# SensorInAmp.net
KiCad netlist of a schematic drawn in Altium Designer
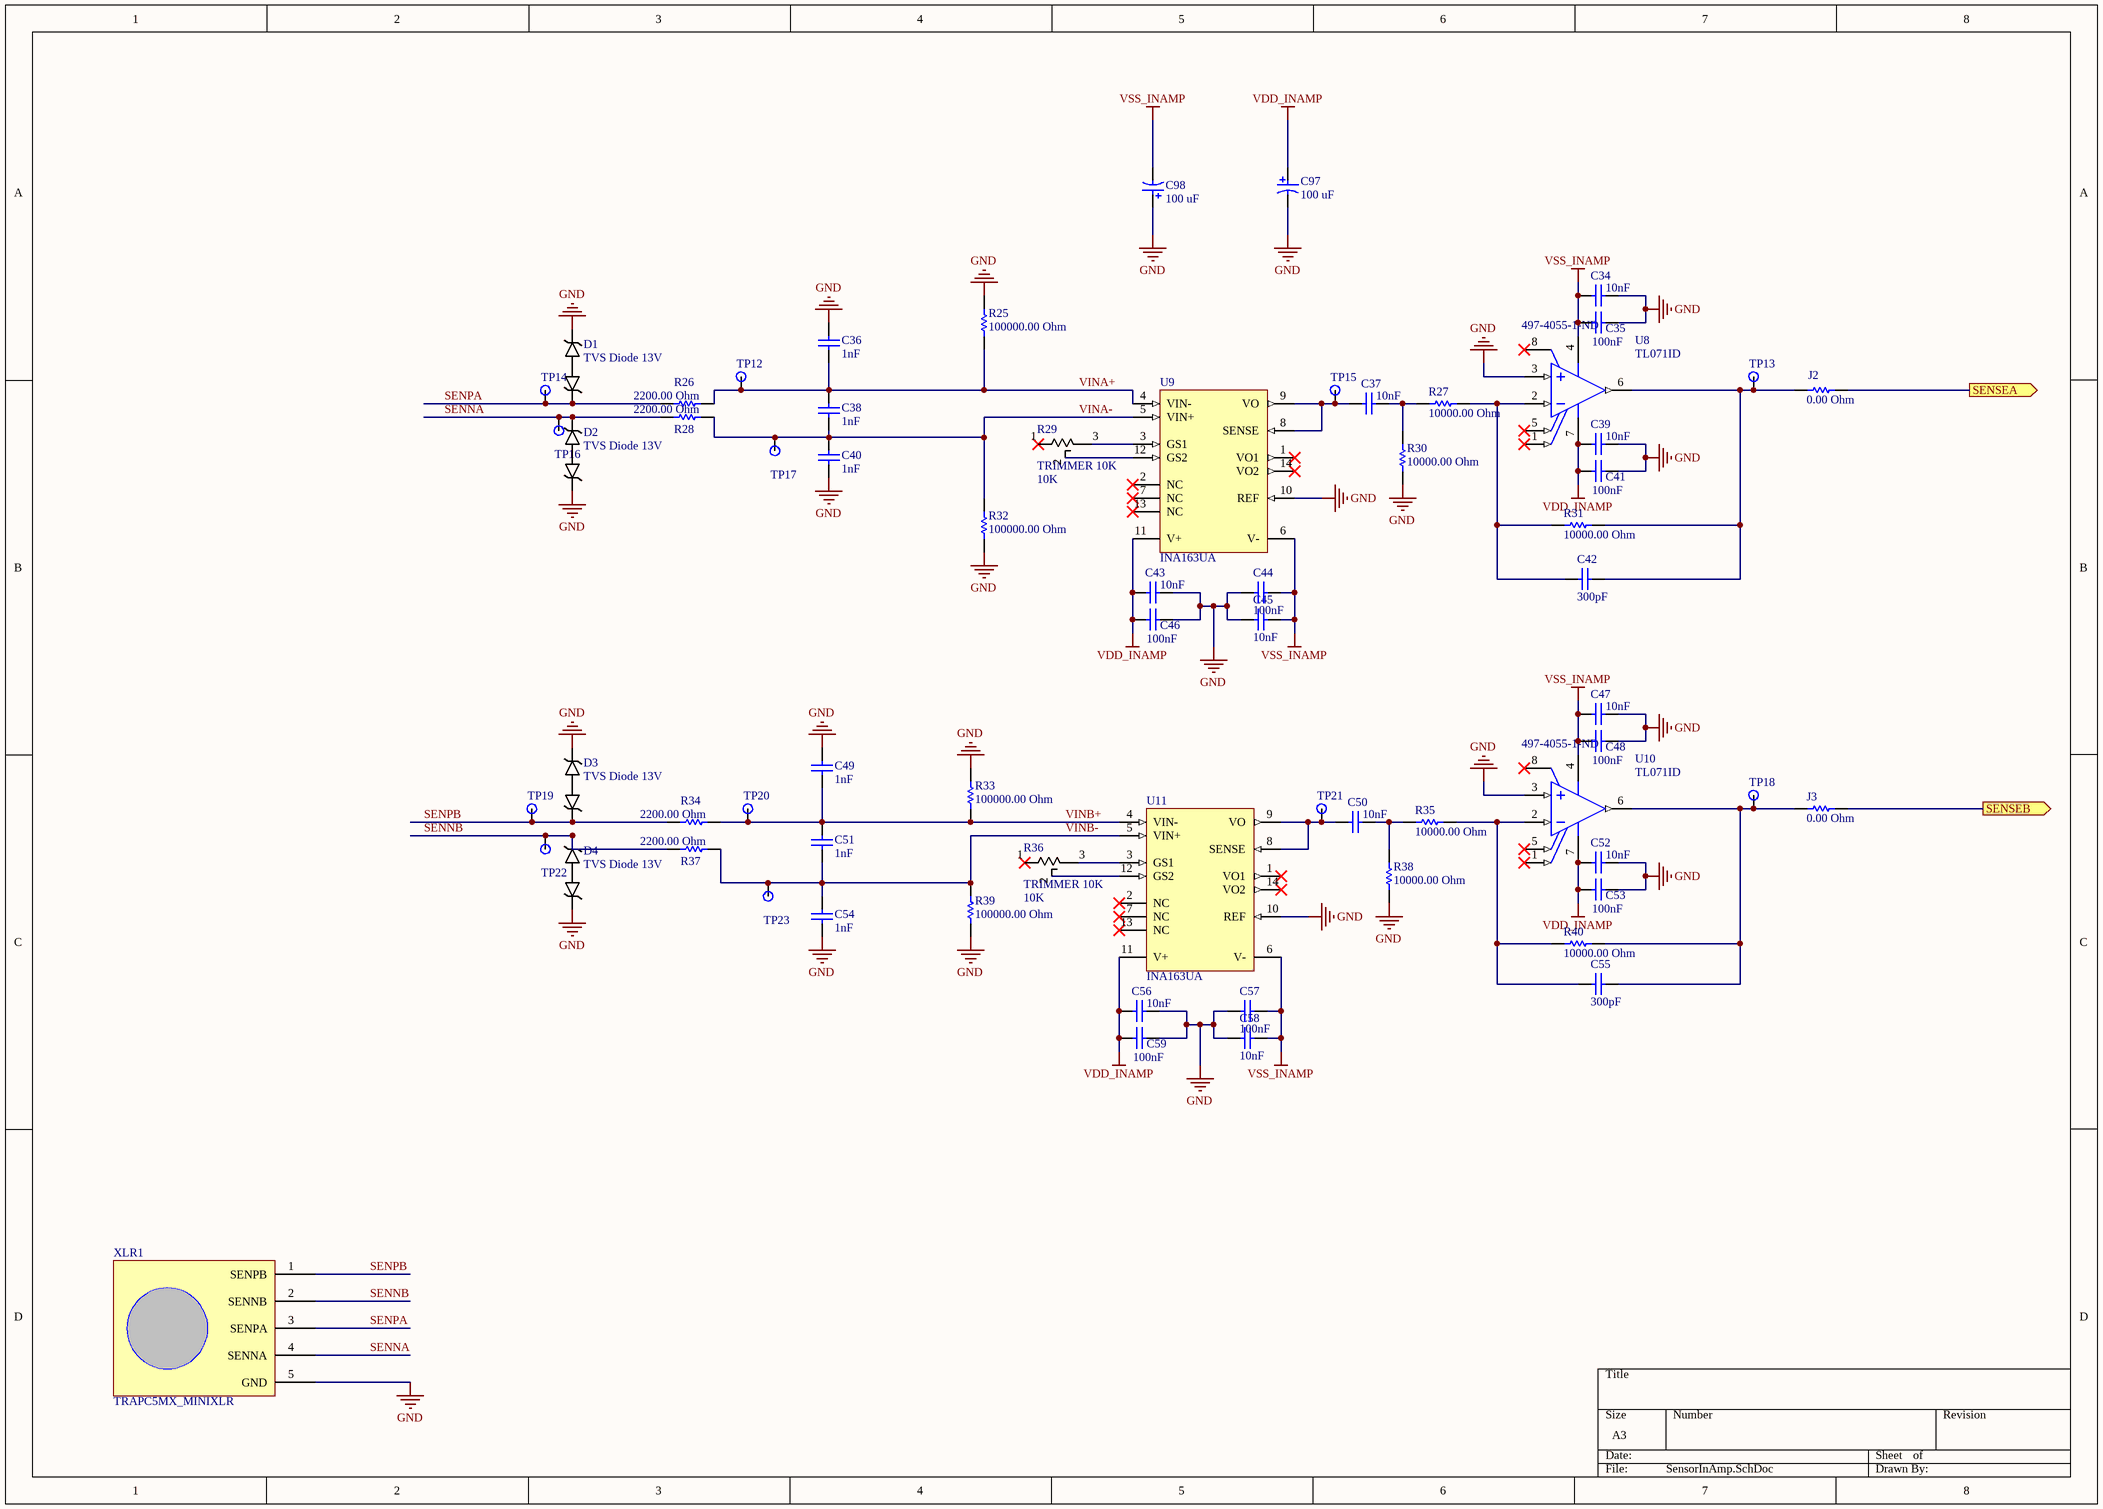
[diagram p0: SensorInAmp.SchDoc]

(export (version "E")
  (design (tool "Eeschema 10.0.6"))
  (components
    (comp (ref "C34")
      (value "10nF")
      (footprint "CAPC0603(1608)100_N")
      (description "CAP 10nF 25V ±10% 0603 (1608 Metric) Thickness 1mm SMD")
      (fields (field (name "TOLERANCE") "Â±10%") (field (name "Comment") "CAP 10nF 25V 0603(1608)"))
      (libsource (lib "Altium Content Vault") (part "CMP-1035-02317-1"))
    )
    (comp (ref "C35")
      (value "100nF")
      (footprint "CAPC0603(1608)100_M")
      (description "CAP 100nF 25V ±10% 0603 (1608 Metric) Thickness 1mm SMD")
      (fields (field (name "TOLERANCE") "Â±10%") (field (name "Comment") "CAP 100nF 25V 0603(1608)"))
      (libsource (lib "Altium Content Vault") (part "CMP-1035-02588-1"))
    )
    (comp (ref "C36")
      (value "1nF")
      (footprint "CAPC0603(1608)100_M")
      (description "CAP 1nF 25V ±5% 0603 (1608 Metric) Thickness 1mm SMD")
      (fields (field (name "TOLERANCE") "Â±5%") (field (name "Comment") "CAP 1nF 25V 0603(1608)"))
      (libsource (lib "Altium Content Vault") (part "CMP-1035-01883-1"))
    )
    (comp (ref "C37")
      (value "10nF")
      (footprint "CAPC0603(1608)100_N")
      (description "CAP 10nF 25V ±10% 0603 (1608 Metric) Thickness 1mm SMD")
      (fields (field (name "TOLERANCE") "Â±10%") (field (name "Comment") "CAP 10nF 25V 0603(1608)"))
      (libsource (lib "Altium Content Vault") (part "CMP-1035-02317-1"))
    )
    (comp (ref "C38")
      (value "1nF")
      (footprint "CAPC0603(1608)100_M")
      (description "CAP 1nF 25V ±5% 0603 (1608 Metric) Thickness 1mm SMD")
      (fields (field (name "TOLERANCE") "Â±5%") (field (name "Comment") "CAP 1nF 25V 0603(1608)"))
      (libsource (lib "Altium Content Vault") (part "CMP-1035-01883-1"))
    )
    (comp (ref "C39")
      (value "10nF")
      (footprint "CAPC0603(1608)100_N")
      (description "CAP 10nF 25V ±10% 0603 (1608 Metric) Thickness 1mm SMD")
      (fields (field (name "TOLERANCE") "Â±10%") (field (name "Comment") "CAP 10nF 25V 0603(1608)"))
      (libsource (lib "Altium Content Vault") (part "CMP-1035-02317-1"))
    )
    (comp (ref "C40")
      (value "1nF")
      (footprint "CAPC0603(1608)100_M")
      (description "CAP 1nF 25V ±5% 0603 (1608 Metric) Thickness 1mm SMD")
      (fields (field (name "TOLERANCE") "Â±5%") (field (name "Comment") "CAP 1nF 25V 0603(1608)"))
      (libsource (lib "Altium Content Vault") (part "CMP-1035-01883-1"))
    )
    (comp (ref "C41")
      (value "100nF")
      (footprint "CAPC0603(1608)100_M")
      (description "CAP 100nF 25V ±10% 0603 (1608 Metric) Thickness 1mm SMD")
      (fields (field (name "TOLERANCE") "Â±10%") (field (name "Comment") "CAP 100nF 25V 0603(1608)"))
      (libsource (lib "Altium Content Vault") (part "CMP-1035-02588-1"))
    )
    (comp (ref "C42")
      (value "300pF")
      (footprint "CAPC0603(1608)100_N")
      (description "CAP 300pF 25V ±10% 0603 (1608 Metric) Thickness 1mm SMD")
      (fields (field (name "TOLERANCE") "Â±10%") (field (name "Comment") "CAP 300pF 25V 0603(1608)"))
      (libsource (lib "Altium Content Vault") (part "CMP-1035-01546-1"))
    )
    (comp (ref "C43")
      (value "10nF")
      (footprint "CAPC0603(1608)100_N")
      (description "CAP 10nF 25V ±10% 0603 (1608 Metric) Thickness 1mm SMD")
      (fields (field (name "TOLERANCE") "Â±10%") (field (name "Comment") "CAP 10nF 25V 0603(1608)"))
      (libsource (lib "Altium Content Vault") (part "CMP-1035-02317-1"))
    )
    (comp (ref "C44")
      (value "100nF")
      (footprint "CAPC0603(1608)100_M")
      (description "CAP 100nF 25V ±10% 0603 (1608 Metric) Thickness 1mm SMD")
      (fields (field (name "TOLERANCE") "Â±10%") (field (name "Comment") "CAP 100nF 25V 0603(1608)"))
      (libsource (lib "Altium Content Vault") (part "CMP-1035-02588-1"))
    )
    (comp (ref "C45")
      (value "10nF")
      (footprint "CAPC0603(1608)100_N")
      (description "CAP 10nF 25V ±10% 0603 (1608 Metric) Thickness 1mm SMD")
      (fields (field (name "TOLERANCE") "Â±10%") (field (name "Comment") "CAP 10nF 25V 0603(1608)"))
      (libsource (lib "Altium Content Vault") (part "CMP-1035-02317-1"))
    )
    (comp (ref "C46")
      (value "100nF")
      (footprint "CAPC0603(1608)100_M")
      (description "CAP 100nF 25V ±10% 0603 (1608 Metric) Thickness 1mm SMD")
      (fields (field (name "TOLERANCE") "Â±10%") (field (name "Comment") "CAP 100nF 25V 0603(1608)"))
      (libsource (lib "Altium Content Vault") (part "CMP-1035-02588-1"))
    )
    (comp (ref "C47")
      (value "10nF")
      (footprint "CAPC0603(1608)100_N")
      (description "CAP 10nF 25V ±10% 0603 (1608 Metric) Thickness 1mm SMD")
      (fields (field (name "TOLERANCE") "Â±10%") (field (name "Comment") "CAP 10nF 25V 0603(1608)"))
      (libsource (lib "Altium Content Vault") (part "CMP-1035-02317-1"))
    )
    (comp (ref "C48")
      (value "100nF")
      (footprint "CAPC0603(1608)100_M")
      (description "CAP 100nF 25V ±10% 0603 (1608 Metric) Thickness 1mm SMD")
      (fields (field (name "TOLERANCE") "Â±10%") (field (name "Comment") "CAP 100nF 25V 0603(1608)"))
      (libsource (lib "Altium Content Vault") (part "CMP-1035-02588-1"))
    )
    (comp (ref "C49")
      (value "1nF")
      (footprint "CAPC0603(1608)100_M")
      (description "CAP 1nF 25V ±5% 0603 (1608 Metric) Thickness 1mm SMD")
      (fields (field (name "TOLERANCE") "Â±5%") (field (name "Comment") "CAP 1nF 25V 0603(1608)"))
      (libsource (lib "Altium Content Vault") (part "CMP-1035-01883-1"))
    )
    (comp (ref "C50")
      (value "10nF")
      (footprint "CAPC0603(1608)100_N")
      (description "CAP 10nF 25V ±10% 0603 (1608 Metric) Thickness 1mm SMD")
      (fields (field (name "TOLERANCE") "Â±10%") (field (name "Comment") "CAP 10nF 25V 0603(1608)"))
      (libsource (lib "Altium Content Vault") (part "CMP-1035-02317-1"))
    )
    (comp (ref "C51")
      (value "1nF")
      (footprint "CAPC0603(1608)100_M")
      (description "CAP 1nF 25V ±5% 0603 (1608 Metric) Thickness 1mm SMD")
      (fields (field (name "TOLERANCE") "Â±5%") (field (name "Comment") "CAP 1nF 25V 0603(1608)"))
      (libsource (lib "Altium Content Vault") (part "CMP-1035-01883-1"))
    )
    (comp (ref "C52")
      (value "10nF")
      (footprint "CAPC0603(1608)100_N")
      (description "CAP 10nF 25V ±10% 0603 (1608 Metric) Thickness 1mm SMD")
      (fields (field (name "TOLERANCE") "Â±10%") (field (name "Comment") "CAP 10nF 25V 0603(1608)"))
      (libsource (lib "Altium Content Vault") (part "CMP-1035-02317-1"))
    )
    (comp (ref "C53")
      (value "100nF")
      (footprint "CAPC0603(1608)100_M")
      (description "CAP 100nF 25V ±10% 0603 (1608 Metric) Thickness 1mm SMD")
      (fields (field (name "TOLERANCE") "Â±10%") (field (name "Comment") "CAP 100nF 25V 0603(1608)"))
      (libsource (lib "Altium Content Vault") (part "CMP-1035-02588-1"))
    )
    (comp (ref "C54")
      (value "1nF")
      (footprint "CAPC0603(1608)100_M")
      (description "CAP 1nF 25V ±5% 0603 (1608 Metric) Thickness 1mm SMD")
      (fields (field (name "TOLERANCE") "Â±5%") (field (name "Comment") "CAP 1nF 25V 0603(1608)"))
      (libsource (lib "Altium Content Vault") (part "CMP-1035-01883-1"))
    )
    (comp (ref "C55")
      (value "300pF")
      (footprint "CAPC0603(1608)100_N")
      (description "CAP 300pF 25V ±10% 0603 (1608 Metric) Thickness 1mm SMD")
      (fields (field (name "TOLERANCE") "Â±10%") (field (name "Comment") "CAP 300pF 25V 0603(1608)"))
      (libsource (lib "Altium Content Vault") (part "CMP-1035-01546-1"))
    )
    (comp (ref "C56")
      (value "10nF")
      (footprint "CAPC0603(1608)100_N")
      (description "CAP 10nF 25V ±10% 0603 (1608 Metric) Thickness 1mm SMD")
      (fields (field (name "TOLERANCE") "Â±10%") (field (name "Comment") "CAP 10nF 25V 0603(1608)"))
      (libsource (lib "Altium Content Vault") (part "CMP-1035-02317-1"))
    )
    (comp (ref "C57")
      (value "100nF")
      (footprint "CAPC0603(1608)100_M")
      (description "CAP 100nF 25V ±10% 0603 (1608 Metric) Thickness 1mm SMD")
      (fields (field (name "TOLERANCE") "Â±10%") (field (name "Comment") "CAP 100nF 25V 0603(1608)"))
      (libsource (lib "Altium Content Vault") (part "CMP-1035-02588-1"))
    )
    (comp (ref "C58")
      (value "10nF")
      (footprint "CAPC0603(1608)100_N")
      (description "CAP 10nF 25V ±10% 0603 (1608 Metric) Thickness 1mm SMD")
      (fields (field (name "TOLERANCE") "Â±10%") (field (name "Comment") "CAP 10nF 25V 0603(1608)"))
      (libsource (lib "Altium Content Vault") (part "CMP-1035-02317-1"))
    )
    (comp (ref "C59")
      (value "100nF")
      (footprint "CAPC0603(1608)100_M")
      (description "CAP 100nF 25V ±10% 0603 (1608 Metric) Thickness 1mm SMD")
      (fields (field (name "TOLERANCE") "Â±10%") (field (name "Comment") "CAP 100nF 25V 0603(1608)"))
      (libsource (lib "Altium Content Vault") (part "CMP-1035-02588-1"))
    )
    (comp (ref "C97")
      (value "100 uF")
      (footprint "CAPPR55-250-1120X630X1220")
      (fields (field (name "MANUFACTURER") "Panasonic"))
      (libsource (lib "Altium Content Vault") (part "CMP-1665-00015-4"))
    )
    (comp (ref "C98")
      (value "100 uF")
      (footprint "CAPPR55-250-1120X630X1220")
      (fields (field (name "MANUFACTURER") "Panasonic"))
      (libsource (lib "Altium Content Vault") (part "CMP-1665-00015-4"))
    )
    (comp (ref "D1")
      (value "TVS Diode 13V")
      (footprint "CPDUR5V0R-HF")
      (description "TVS DIODE 5VWM 13VC SOD-523F")
      (fields
        (field (name "MANUFACTURER") "Comchip Technology")
        (field (name "MANUFACTURER PART NUMBER") "CPDUR5V0R-HF")
        (field (name "PUBLISHER") "Altium Limited")
      )
      (libsource (lib "AnserEMT") (part "CPDUR5V0R-HF"))
    )
    (comp (ref "D2")
      (value "TVS Diode 13V")
      (footprint "CPDUR5V0R-HF")
      (description "TVS DIODE 5VWM 13VC SOD-523F")
      (fields
        (field (name "MANUFACTURER") "Comchip Technology")
        (field (name "MANUFACTURER PART NUMBER") "CPDUR5V0R-HF")
        (field (name "PUBLISHER") "Altium Limited")
      )
      (libsource (lib "AnserEMT") (part "CPDUR5V0R-HF"))
    )
    (comp (ref "D3")
      (value "TVS Diode 13V")
      (footprint "CPDUR5V0R-HF")
      (description "TVS DIODE 5VWM 13VC SOD-523F")
      (fields
        (field (name "MANUFACTURER") "Comchip Technology")
        (field (name "MANUFACTURER PART NUMBER") "CPDUR5V0R-HF")
        (field (name "PUBLISHER") "Altium Limited")
      )
      (libsource (lib "AnserEMT") (part "CPDUR5V0R-HF"))
    )
    (comp (ref "D4")
      (value "TVS Diode 13V")
      (footprint "CPDUR5V0R-HF")
      (description "TVS DIODE 5VWM 13VC SOD-523F")
      (fields
        (field (name "MANUFACTURER") "Comchip Technology")
        (field (name "MANUFACTURER PART NUMBER") "CPDUR5V0R-HF")
        (field (name "PUBLISHER") "Altium Limited")
      )
      (libsource (lib "AnserEMT") (part "CPDUR5V0R-HF"))
    )
    (comp (ref "J2")
      (value "0.00 Ohm")
      (footprint "RESC1206(3216)_M")
      (description "Jumper 1206 (3216 Metric)")
      (fields (field (name "TOLERANCE") "None"))
      (libsource (lib "Altium Content Vault") (part "CMP-1014-00001-1"))
    )
    (comp (ref "J3")
      (value "0.00 Ohm")
      (footprint "RESC1206(3216)_M")
      (description "Jumper 1206 (3216 Metric)")
      (fields (field (name "TOLERANCE") "None"))
      (libsource (lib "Altium Content Vault") (part "CMP-1014-00001-1"))
    )
    (comp (ref "R25")
      (value "100000.00 Ohm")
      (footprint "RESC0603(1608)_N")
      (description "100K 0.1W 5% 0603 (1608 Metric)  SMD")
      (fields (field (name "TOLERANCE") "5 %") (field (name "POWER") "0.1 W"))
      (libsource (lib "Altium Content Vault") (part "CMP-1012-00122-1"))
    )
    (comp (ref "R26")
      (value "2200.00 Ohm")
      (footprint "RESC0603(1608)_L")
      (description "2K2 0.1W 1% 0603 (1608 Metric)  SMD")
      (fields (field (name "TOLERANCE") "1 %") (field (name "POWER") "0.1 W"))
      (libsource (lib "Altium Content Vault") (part "CMP-1012-00546-1"))
    )
    (comp (ref "R27")
      (value "10000.00 Ohm")
      (footprint "RESC0603(1608)_N")
      (description "10K 0.1W 5% 0603 (1608 Metric)  SMD")
      (fields (field (name "TOLERANCE") "5 %") (field (name "POWER") "0.1 W"))
      (libsource (lib "Altium Content Vault") (part "CMP-1012-00098-1"))
    )
    (comp (ref "R28")
      (value "2200.00 Ohm")
      (footprint "RESC0603(1608)_L")
      (description "2K2 0.1W 1% 0603 (1608 Metric)  SMD")
      (fields (field (name "TOLERANCE") "1 %") (field (name "POWER") "0.1 W"))
      (libsource (lib "Altium Content Vault") (part "CMP-1012-00546-1"))
    )
    (comp (ref "R29")
      (value "TRIMMER 10K")
      (footprint "TRIMMER 10K")
      (description "TRIMMER 10K OHM 0.5W TH")
      (fields
        (field (name "MANUFACTURER") "TE Connectivity Passive Product")
        (field (name "MANUFACTURER PART NUMBER") "1-1623849-0")
        (field (name "ALTIUM_VALUE") "10K")
        (field (name "PUBLISHER") "Altium Limited")
      )
      (libsource (lib "AnserEMT") (part "TRIMMER 10K"))
    )
    (comp (ref "R30")
      (value "10000.00 Ohm")
      (footprint "RESC0603(1608)_N")
      (description "10K 0.1W 5% 0603 (1608 Metric)  SMD")
      (fields (field (name "TOLERANCE") "5 %") (field (name "POWER") "0.1 W"))
      (libsource (lib "Altium Content Vault") (part "CMP-1012-00098-1"))
    )
    (comp (ref "R31")
      (value "10000.00 Ohm")
      (footprint "RESC0603(1608)_N")
      (description "10K 0.1W 5% 0603 (1608 Metric)  SMD")
      (fields (field (name "TOLERANCE") "5 %") (field (name "POWER") "0.1 W"))
      (libsource (lib "Altium Content Vault") (part "CMP-1012-00098-1"))
    )
    (comp (ref "R32")
      (value "100000.00 Ohm")
      (footprint "RESC0603(1608)_N")
      (description "100K 0.1W 5% 0603 (1608 Metric)  SMD")
      (fields (field (name "TOLERANCE") "5 %") (field (name "POWER") "0.1 W"))
      (libsource (lib "Altium Content Vault") (part "CMP-1012-00122-1"))
    )
    (comp (ref "R33")
      (value "100000.00 Ohm")
      (footprint "RESC0603(1608)_N")
      (description "100K 0.1W 5% 0603 (1608 Metric)  SMD")
      (fields (field (name "TOLERANCE") "5 %") (field (name "POWER") "0.1 W"))
      (libsource (lib "Altium Content Vault") (part "CMP-1012-00122-1"))
    )
    (comp (ref "R34")
      (value "2200.00 Ohm")
      (footprint "RESC0603(1608)_L")
      (description "2K2 0.1W 1% 0603 (1608 Metric)  SMD")
      (fields (field (name "TOLERANCE") "1 %") (field (name "POWER") "0.1 W"))
      (libsource (lib "Altium Content Vault") (part "CMP-1012-00546-1"))
    )
    (comp (ref "R35")
      (value "10000.00 Ohm")
      (footprint "RESC0603(1608)_N")
      (description "10K 0.1W 5% 0603 (1608 Metric)  SMD")
      (fields (field (name "TOLERANCE") "5 %") (field (name "POWER") "0.1 W"))
      (libsource (lib "Altium Content Vault") (part "CMP-1012-00098-1"))
    )
    (comp (ref "R36")
      (value "TRIMMER 10K")
      (footprint "TRIMMER 10K")
      (description "TRIMMER 10K OHM 0.5W TH")
      (fields
        (field (name "MANUFACTURER") "TE Connectivity Passive Product")
        (field (name "MANUFACTURER PART NUMBER") "1-1623849-0")
        (field (name "ALTIUM_VALUE") "10K")
        (field (name "PUBLISHER") "Altium Limited")
      )
      (libsource (lib "AnserEMT") (part "TRIMMER 10K"))
    )
    (comp (ref "R37")
      (value "2200.00 Ohm")
      (footprint "RESC0603(1608)_L")
      (description "2K2 0.1W 1% 0603 (1608 Metric)  SMD")
      (fields (field (name "TOLERANCE") "1 %") (field (name "POWER") "0.1 W"))
      (libsource (lib "Altium Content Vault") (part "CMP-1012-00546-1"))
    )
    (comp (ref "R38")
      (value "10000.00 Ohm")
      (footprint "RESC0603(1608)_N")
      (description "10K 0.1W 5% 0603 (1608 Metric)  SMD")
      (fields (field (name "TOLERANCE") "5 %") (field (name "POWER") "0.1 W"))
      (libsource (lib "Altium Content Vault") (part "CMP-1012-00098-1"))
    )
    (comp (ref "R39")
      (value "100000.00 Ohm")
      (footprint "RESC0603(1608)_N")
      (description "100K 0.1W 5% 0603 (1608 Metric)  SMD")
      (fields (field (name "TOLERANCE") "5 %") (field (name "POWER") "0.1 W"))
      (libsource (lib "Altium Content Vault") (part "CMP-1012-00122-1"))
    )
    (comp (ref "R40")
      (value "10000.00 Ohm")
      (footprint "RESC0603(1608)_N")
      (description "10K 0.1W 5% 0603 (1608 Metric)  SMD")
      (fields (field (name "TOLERANCE") "5 %") (field (name "POWER") "0.1 W"))
      (libsource (lib "Altium Content Vault") (part "CMP-1012-00098-1"))
    )
    (comp (ref "TP12")
      (value "Testpoint")
      (footprint "0603 PROBE PAD")
      (description "0.063\" x 0.031\" x 0.045\" (1.60mm x 0.80mm x 1.15mm)")
      (libsource (lib "testpoint") (part "Testpoint"))
    )
    (comp (ref "TP13")
      (value "Testpoint")
      (footprint "0603 PROBE PAD")
      (description "0.063\" x 0.031\" x 0.045\" (1.60mm x 0.80mm x 1.15mm)")
      (libsource (lib "testpoint") (part "Testpoint"))
    )
    (comp (ref "TP14")
      (value "Testpoint")
      (footprint "0603 PROBE PAD")
      (description "0.063\" x 0.031\" x 0.045\" (1.60mm x 0.80mm x 1.15mm)")
      (libsource (lib "testpoint") (part "Testpoint"))
    )
    (comp (ref "TP15")
      (value "Testpoint")
      (footprint "0603 PROBE PAD")
      (description "0.063\" x 0.031\" x 0.045\" (1.60mm x 0.80mm x 1.15mm)")
      (libsource (lib "testpoint") (part "Testpoint"))
    )
    (comp (ref "TP16")
      (value "Testpoint")
      (footprint "0603 PROBE PAD")
      (description "0.063\" x 0.031\" x 0.045\" (1.60mm x 0.80mm x 1.15mm)")
      (libsource (lib "testpoint") (part "Testpoint"))
    )
    (comp (ref "TP17")
      (value "Testpoint")
      (footprint "0603 PROBE PAD")
      (description "0.063\" x 0.031\" x 0.045\" (1.60mm x 0.80mm x 1.15mm)")
      (libsource (lib "testpoint") (part "Testpoint"))
    )
    (comp (ref "TP18")
      (value "Testpoint")
      (footprint "0603 PROBE PAD")
      (description "0.063\" x 0.031\" x 0.045\" (1.60mm x 0.80mm x 1.15mm)")
      (libsource (lib "testpoint") (part "Testpoint"))
    )
    (comp (ref "TP19")
      (value "Testpoint")
      (footprint "0603 PROBE PAD")
      (description "0.063\" x 0.031\" x 0.045\" (1.60mm x 0.80mm x 1.15mm)")
      (libsource (lib "testpoint") (part "Testpoint"))
    )
    (comp (ref "TP20")
      (value "Testpoint")
      (footprint "0603 PROBE PAD")
      (description "0.063\" x 0.031\" x 0.045\" (1.60mm x 0.80mm x 1.15mm)")
      (libsource (lib "testpoint") (part "Testpoint"))
    )
    (comp (ref "TP21")
      (value "Testpoint")
      (footprint "0603 PROBE PAD")
      (description "0.063\" x 0.031\" x 0.045\" (1.60mm x 0.80mm x 1.15mm)")
      (libsource (lib "testpoint") (part "Testpoint"))
    )
    (comp (ref "TP22")
      (value "Testpoint")
      (footprint "0603 PROBE PAD")
      (description "0.063\" x 0.031\" x 0.045\" (1.60mm x 0.80mm x 1.15mm)")
      (libsource (lib "testpoint") (part "Testpoint"))
    )
    (comp (ref "TP23")
      (value "Testpoint")
      (footprint "0603 PROBE PAD")
      (description "0.063\" x 0.031\" x 0.045\" (1.60mm x 0.80mm x 1.15mm)")
      (libsource (lib "testpoint") (part "Testpoint"))
    )
    (comp (ref "U8")
      (value "TL071ID")
      (footprint "D0008A_L")
      (fields
        (field (name "MANUFACTURER") "Texas Instruments")
        (field (name "SUPPLIER PART NUMBER 1") "497-4055-1-ND")
        (field (name "MANUFACTURER PART NUMBER") "TL071CDT")
      )
      (libsource (lib "Altium Content Vault") (part "CMP-0017-00492-2"))
    )
    (comp (ref "U9")
      (value "INA163UA")
      (footprint "D0014A_L")
      (fields (field (name "MANUFACTURER") "Texas Instruments"))
      (libsource (lib "Altium Content Vault") (part "CMP-0944-00013-2"))
    )
    (comp (ref "U10")
      (value "TL071ID")
      (footprint "D0008A_L")
      (fields
        (field (name "MANUFACTURER") "Texas Instruments")
        (field (name "SUPPLIER PART NUMBER 1") "497-4055-1-ND")
        (field (name "MANUFACTURER PART NUMBER") "TL071CDT")
      )
      (libsource (lib "Altium Content Vault") (part "CMP-0017-00492-2"))
    )
    (comp (ref "U11")
      (value "INA163UA")
      (footprint "D0014A_L")
      (fields (field (name "MANUFACTURER") "Texas Instruments"))
      (libsource (lib "Altium Content Vault") (part "CMP-0944-00013-2"))
    )
    (comp (ref "XLR1")
      (value "TRAPC5MX_MINIXLR")
      (footprint "MiniXLR_TRAPC5MX_5POS")
      (description "CONN RCPT 5POS R/A MALE T/H")
      (fields
        (field (name "MANUFACTURER") "Switchcraft Inc.")
        (field (name "MANUFACTURER PART NUMBER") "TRAPC5MX")
        (field (name "PUBLISHER") "Altium Limited")
      )
      (libsource (lib "AnserEMT") (part "TRAPC5MX_MINIXLR"))
    )
  )
  (nets
    (net (code "1") (name "/SENNA") (class "Default")
      (node (ref "D2") (pin "2") (pintype "passive"))
      (node (ref "R28") (pin "2") (pinfunction "2_2") (pintype "passive"))
      (node (ref "TP16") (pin "0") (pintype "passive"))
      (node (ref "XLR1") (pin "4") (pinfunction "SENNA_4") (pintype "passive"))
    )
    (net (code "2") (name "/SENNB") (class "Default")
      (node (ref "D4") (pin "2") (pintype "passive"))
      (node (ref "R37") (pin "2") (pinfunction "2_2") (pintype "passive"))
      (node (ref "TP22") (pin "0") (pintype "passive"))
      (node (ref "XLR1") (pin "2") (pinfunction "SENNB_2") (pintype "passive"))
    )
    (net (code "3") (name "/SENPA") (class "Default")
      (node (ref "D1") (pin "1") (pintype "passive"))
      (node (ref "R26") (pin "2") (pinfunction "2_2") (pintype "passive"))
      (node (ref "TP14") (pin "0") (pintype "passive"))
      (node (ref "XLR1") (pin "3") (pinfunction "SENPA_3") (pintype "passive"))
    )
    (net (code "4") (name "/SENPB") (class "Default")
      (node (ref "D3") (pin "1") (pintype "passive"))
      (node (ref "R34") (pin "2") (pinfunction "2_2") (pintype "passive"))
      (node (ref "TP19") (pin "0") (pintype "passive"))
      (node (ref "XLR1") (pin "1") (pinfunction "SENPB_1") (pintype "power_in"))
    )
    (net (code "5") (name "/SENSEA") (class "Default")
      (node (ref "J2") (pin "2") (pinfunction "2_2") (pintype "passive"))
    )
    (net (code "6") (name "/SENSEB") (class "Default")
      (node (ref "J3") (pin "2") (pinfunction "2_2") (pintype "passive"))
    )
    (net (code "7") (name "/VINA+") (class "Default")
      (node (ref "C36") (pin "1") (pinfunction "1_1") (pintype "passive"))
      (node (ref "C38") (pin "2") (pinfunction "2_2") (pintype "passive"))
      (node (ref "R25") (pin "2") (pinfunction "2_2") (pintype "passive"))
      (node (ref "R26") (pin "1") (pinfunction "1_1") (pintype "passive"))
      (node (ref "TP12") (pin "0") (pintype "passive"))
      (node (ref "U9") (pin "4") (pinfunction "VIN-_4") (pintype "input"))
    )
    (net (code "8") (name "/VINA-") (class "Default")
      (node (ref "C38") (pin "1") (pinfunction "1_1") (pintype "passive"))
      (node (ref "C40") (pin "2") (pinfunction "2_2") (pintype "passive"))
      (node (ref "R28") (pin "1") (pinfunction "1_1") (pintype "passive"))
      (node (ref "R32") (pin "1") (pinfunction "1_1") (pintype "passive"))
      (node (ref "TP17") (pin "0") (pintype "passive"))
      (node (ref "U9") (pin "5") (pinfunction "VIN+_5") (pintype "input"))
    )
    (net (code "9") (name "/VINB+") (class "Default")
      (node (ref "C49") (pin "1") (pinfunction "1_1") (pintype "passive"))
      (node (ref "C51") (pin "2") (pinfunction "2_2") (pintype "passive"))
      (node (ref "R33") (pin "2") (pinfunction "2_2") (pintype "passive"))
      (node (ref "R34") (pin "1") (pinfunction "1_1") (pintype "passive"))
      (node (ref "TP20") (pin "0") (pintype "passive"))
      (node (ref "U11") (pin "4") (pinfunction "VIN-_4") (pintype "input"))
    )
    (net (code "10") (name "/VINB-") (class "Default")
      (node (ref "C51") (pin "1") (pinfunction "1_1") (pintype "passive"))
      (node (ref "C54") (pin "2") (pinfunction "2_2") (pintype "passive"))
      (node (ref "R37") (pin "1") (pinfunction "1_1") (pintype "passive"))
      (node (ref "R39") (pin "1") (pinfunction "1_1") (pintype "passive"))
      (node (ref "TP23") (pin "0") (pintype "passive"))
      (node (ref "U11") (pin "5") (pinfunction "VIN+_5") (pintype "input"))
    )
    (net (code "11") (name "GND") (class "Default")
      (node (ref "C34") (pin "2") (pinfunction "2_2") (pintype "passive"))
      (node (ref "C35") (pin "1") (pinfunction "1_1") (pintype "passive"))
      (node (ref "C36") (pin "2") (pinfunction "2_2") (pintype "passive"))
      (node (ref "C39") (pin "2") (pinfunction "2_2") (pintype "passive"))
      (node (ref "C40") (pin "1") (pinfunction "1_1") (pintype "passive"))
      (node (ref "C41") (pin "1") (pinfunction "1_1") (pintype "passive"))
      (node (ref "C43") (pin "2") (pinfunction "2_2") (pintype "passive"))
      (node (ref "C44") (pin "1") (pinfunction "1_1") (pintype "passive"))
      (node (ref "C45") (pin "2") (pinfunction "2_2") (pintype "passive"))
      (node (ref "C46") (pin "1") (pinfunction "1_1") (pintype "passive"))
      (node (ref "C47") (pin "2") (pinfunction "2_2") (pintype "passive"))
      (node (ref "C48") (pin "1") (pinfunction "1_1") (pintype "passive"))
      (node (ref "C49") (pin "2") (pinfunction "2_2") (pintype "passive"))
      (node (ref "C52") (pin "2") (pinfunction "2_2") (pintype "passive"))
      (node (ref "C53") (pin "1") (pinfunction "1_1") (pintype "passive"))
      (node (ref "C54") (pin "1") (pinfunction "1_1") (pintype "passive"))
      (node (ref "C56") (pin "2") (pinfunction "2_2") (pintype "passive"))
      (node (ref "C57") (pin "1") (pinfunction "1_1") (pintype "passive"))
      (node (ref "C58") (pin "2") (pinfunction "2_2") (pintype "passive"))
      (node (ref "C59") (pin "1") (pinfunction "1_1") (pintype "passive"))
      (node (ref "C97") (pin "2") (pinfunction "2_2") (pintype "passive"))
      (node (ref "C98") (pin "1") (pinfunction "1_1") (pintype "passive"))
      (node (ref "D1") (pin "2") (pintype "passive"))
      (node (ref "D2") (pin "1") (pintype "passive"))
      (node (ref "D3") (pin "2") (pintype "passive"))
      (node (ref "D4") (pin "1") (pintype "passive"))
      (node (ref "R25") (pin "1") (pinfunction "1_1") (pintype "passive"))
      (node (ref "R30") (pin "2") (pinfunction "2_2") (pintype "passive"))
      (node (ref "R32") (pin "2") (pinfunction "2_2") (pintype "passive"))
      (node (ref "R33") (pin "1") (pinfunction "1_1") (pintype "passive"))
      (node (ref "R38") (pin "2") (pinfunction "2_2") (pintype "passive"))
      (node (ref "R39") (pin "2") (pinfunction "2_2") (pintype "passive"))
      (node (ref "U10") (pin "3") (pinfunction "IN+_3") (pintype "input"))
      (node (ref "U11") (pin "10") (pinfunction "REF_10") (pintype "input"))
      (node (ref "U8") (pin "3") (pinfunction "IN+_3") (pintype "input"))
      (node (ref "U9") (pin "10") (pinfunction "REF_10") (pintype "input"))
      (node (ref "XLR1") (pin "5") (pinfunction "GND_5") (pintype "passive"))
    )
    (net (code "12") (name "Net-(C37-Pad2)") (class "Default")
      (node (ref "C37") (pin "2") (pinfunction "2_2") (pintype "passive"))
      (node (ref "R27") (pin "2") (pinfunction "2_2") (pintype "passive"))
      (node (ref "R30") (pin "1") (pinfunction "1_1") (pintype "passive"))
    )
    (net (code "13") (name "Net-(C50-Pad2)") (class "Default")
      (node (ref "C50") (pin "2") (pinfunction "2_2") (pintype "passive"))
      (node (ref "R35") (pin "2") (pinfunction "2_2") (pintype "passive"))
      (node (ref "R38") (pin "1") (pinfunction "1_1") (pintype "passive"))
    )
    (net (code "14") (name "Net-(U8-IN-)") (class "Default")
      (node (ref "C42") (pin "2") (pinfunction "2_2") (pintype "passive"))
      (node (ref "R27") (pin "1") (pinfunction "1_1") (pintype "passive"))
      (node (ref "R31") (pin "2") (pinfunction "2_2") (pintype "passive"))
      (node (ref "U8") (pin "2") (pinfunction "IN-_2") (pintype "input"))
    )
    (net (code "15") (name "Net-(U8-OUT)") (class "Default")
      (node (ref "C42") (pin "1") (pinfunction "1_1") (pintype "passive"))
      (node (ref "J2") (pin "1") (pinfunction "1_1") (pintype "passive"))
      (node (ref "R31") (pin "1") (pinfunction "1_1") (pintype "passive"))
      (node (ref "TP13") (pin "0") (pintype "passive"))
      (node (ref "U8") (pin "6") (pinfunction "OUT_6") (pintype "output"))
    )
    (net (code "16") (name "Net-(U9-GS1)") (class "Default")
      (node (ref "R29") (pin "3") (pinfunction "3_3") (pintype "passive"))
      (node (ref "U9") (pin "3") (pinfunction "GS1_3") (pintype "input"))
    )
    (net (code "17") (name "Net-(U9-GS2)") (class "Default")
      (node (ref "R29") (pin "2") (pinfunction "2_2") (pintype "passive"))
      (node (ref "U9") (pin "12") (pinfunction "GS2_12") (pintype "input"))
    )
    (net (code "18") (name "Net-(U9-SENSE)") (class "Default")
      (node (ref "C37") (pin "1") (pinfunction "1_1") (pintype "passive"))
      (node (ref "TP15") (pin "0") (pintype "passive"))
      (node (ref "U9") (pin "8") (pinfunction "SENSE_8") (pintype "input"))
      (node (ref "U9") (pin "9") (pinfunction "VO_9") (pintype "output"))
    )
    (net (code "19") (name "Net-(U10-IN-)") (class "Default")
      (node (ref "C55") (pin "2") (pinfunction "2_2") (pintype "passive"))
      (node (ref "R35") (pin "1") (pinfunction "1_1") (pintype "passive"))
      (node (ref "R40") (pin "2") (pinfunction "2_2") (pintype "passive"))
      (node (ref "U10") (pin "2") (pinfunction "IN-_2") (pintype "input"))
    )
    (net (code "20") (name "Net-(U10-OUT)") (class "Default")
      (node (ref "C55") (pin "1") (pinfunction "1_1") (pintype "passive"))
      (node (ref "J3") (pin "1") (pinfunction "1_1") (pintype "passive"))
      (node (ref "R40") (pin "1") (pinfunction "1_1") (pintype "passive"))
      (node (ref "TP18") (pin "0") (pintype "passive"))
      (node (ref "U10") (pin "6") (pinfunction "OUT_6") (pintype "output"))
    )
    (net (code "21") (name "Net-(U11-GS1)") (class "Default")
      (node (ref "R36") (pin "3") (pinfunction "3_3") (pintype "passive"))
      (node (ref "U11") (pin "3") (pinfunction "GS1_3") (pintype "input"))
    )
    (net (code "22") (name "Net-(U11-GS2)") (class "Default")
      (node (ref "R36") (pin "2") (pinfunction "2_2") (pintype "passive"))
      (node (ref "U11") (pin "12") (pinfunction "GS2_12") (pintype "input"))
    )
    (net (code "23") (name "Net-(U11-SENSE)") (class "Default")
      (node (ref "C50") (pin "1") (pinfunction "1_1") (pintype "passive"))
      (node (ref "TP21") (pin "0") (pintype "passive"))
      (node (ref "U11") (pin "8") (pinfunction "SENSE_8") (pintype "input"))
      (node (ref "U11") (pin "9") (pinfunction "VO_9") (pintype "output"))
    )
    (net (code "24") (name "VDD_INAMP") (class "Default")
      (node (ref "C39") (pin "1") (pinfunction "1_1") (pintype "passive"))
      (node (ref "C41") (pin "2") (pinfunction "2_2") (pintype "passive"))
      (node (ref "C43") (pin "1") (pinfunction "1_1") (pintype "passive"))
      (node (ref "C46") (pin "2") (pinfunction "2_2") (pintype "passive"))
      (node (ref "C52") (pin "1") (pinfunction "1_1") (pintype "passive"))
      (node (ref "C53") (pin "2") (pinfunction "2_2") (pintype "passive"))
      (node (ref "C56") (pin "1") (pinfunction "1_1") (pintype "passive"))
      (node (ref "C59") (pin "2") (pinfunction "2_2") (pintype "passive"))
      (node (ref "C97") (pin "1") (pinfunction "1_1") (pintype "passive"))
      (node (ref "U10") (pin "7") (pinfunction "VCC+_7") (pintype "power_in"))
      (node (ref "U11") (pin "11") (pinfunction "V+_11") (pintype "power_in"))
      (node (ref "U8") (pin "7") (pinfunction "VCC+_7") (pintype "power_in"))
      (node (ref "U9") (pin "11") (pinfunction "V+_11") (pintype "power_in"))
    )
    (net (code "25") (name "VSS_INAMP") (class "Default")
      (node (ref "C34") (pin "1") (pinfunction "1_1") (pintype "passive"))
      (node (ref "C35") (pin "2") (pinfunction "2_2") (pintype "passive"))
      (node (ref "C44") (pin "2") (pinfunction "2_2") (pintype "passive"))
      (node (ref "C45") (pin "1") (pinfunction "1_1") (pintype "passive"))
      (node (ref "C47") (pin "1") (pinfunction "1_1") (pintype "passive"))
      (node (ref "C48") (pin "2") (pinfunction "2_2") (pintype "passive"))
      (node (ref "C57") (pin "2") (pinfunction "2_2") (pintype "passive"))
      (node (ref "C58") (pin "1") (pinfunction "1_1") (pintype "passive"))
      (node (ref "C98") (pin "2") (pinfunction "2_2") (pintype "passive"))
      (node (ref "U10") (pin "4") (pinfunction "VCC-_4") (pintype "power_in"))
      (node (ref "U11") (pin "6") (pinfunction "V-_6") (pintype "power_in"))
      (node (ref "U8") (pin "4") (pinfunction "VCC-_4") (pintype "power_in"))
      (node (ref "U9") (pin "6") (pinfunction "V-_6") (pintype "power_in"))
    )
    (net (code "26") (name "unconnected-(R29-Pad1)") (class "Default")
      (node (ref "R29") (pin "1") (pinfunction "1_1") (pintype "passive+no_connect"))
    )
    (net (code "27") (name "unconnected-(R36-Pad1)") (class "Default")
      (node (ref "R36") (pin "1") (pinfunction "1_1") (pintype "passive+no_connect"))
    )
    (net (code "28") (name "unconnected-(U8-NC-Pad8)") (class "Default")
      (node (ref "U8") (pin "8") (pinfunction "NC_8") (pintype "passive+no_connect"))
    )
    (net (code "29") (name "unconnected-(U8-OFFSET_N1-Pad1)") (class "Default")
      (node (ref "U8") (pin "1") (pinfunction "OFFSET_N1_1") (pintype "input+no_connect"))
    )
    (net (code "30") (name "unconnected-(U8-OFFSET_N2-Pad5)") (class "Default")
      (node (ref "U8") (pin "5") (pinfunction "OFFSET_N2_5") (pintype "input+no_connect"))
    )
    (net (code "31") (name "unconnected-(U9-NC-Pad2)") (class "Default")
      (node (ref "U9") (pin "2") (pinfunction "NC_2") (pintype "passive+no_connect"))
    )
    (net (code "32") (name "unconnected-(U9-NC-Pad7)") (class "Default")
      (node (ref "U9") (pin "7") (pinfunction "NC_7") (pintype "passive+no_connect"))
    )
    (net (code "33") (name "unconnected-(U9-NC-Pad13)") (class "Default")
      (node (ref "U9") (pin "13") (pinfunction "NC_13") (pintype "passive+no_connect"))
    )
    (net (code "34") (name "unconnected-(U9-VO1-Pad1)") (class "Default")
      (node (ref "U9") (pin "1") (pinfunction "VO1_1") (pintype "output+no_connect"))
    )
    (net (code "35") (name "unconnected-(U9-VO2-Pad14)") (class "Default")
      (node (ref "U9") (pin "14") (pinfunction "VO2_14") (pintype "output+no_connect"))
    )
    (net (code "36") (name "unconnected-(U10-NC-Pad8)") (class "Default")
      (node (ref "U10") (pin "8") (pinfunction "NC_8") (pintype "passive+no_connect"))
    )
    (net (code "37") (name "unconnected-(U10-OFFSET_N1-Pad1)") (class "Default")
      (node (ref "U10") (pin "1") (pinfunction "OFFSET_N1_1") (pintype "input+no_connect"))
    )
    (net (code "38") (name "unconnected-(U10-OFFSET_N2-Pad5)") (class "Default")
      (node (ref "U10") (pin "5") (pinfunction "OFFSET_N2_5") (pintype "input+no_connect"))
    )
    (net (code "39") (name "unconnected-(U11-NC-Pad2)") (class "Default")
      (node (ref "U11") (pin "2") (pinfunction "NC_2") (pintype "passive+no_connect"))
    )
    (net (code "40") (name "unconnected-(U11-NC-Pad7)") (class "Default")
      (node (ref "U11") (pin "7") (pinfunction "NC_7") (pintype "passive+no_connect"))
    )
    (net (code "41") (name "unconnected-(U11-NC-Pad13)") (class "Default")
      (node (ref "U11") (pin "13") (pinfunction "NC_13") (pintype "passive+no_connect"))
    )
    (net (code "42") (name "unconnected-(U11-VO1-Pad1)") (class "Default")
      (node (ref "U11") (pin "1") (pinfunction "VO1_1") (pintype "output+no_connect"))
    )
    (net (code "43") (name "unconnected-(U11-VO2-Pad14)") (class "Default")
      (node (ref "U11") (pin "14") (pinfunction "VO2_14") (pintype "output+no_connect"))
    )
  )
)
